# wemos_Atmega_32_sensor_tes_2.net
KiCad netlist of a schematic drawn in EAGLE
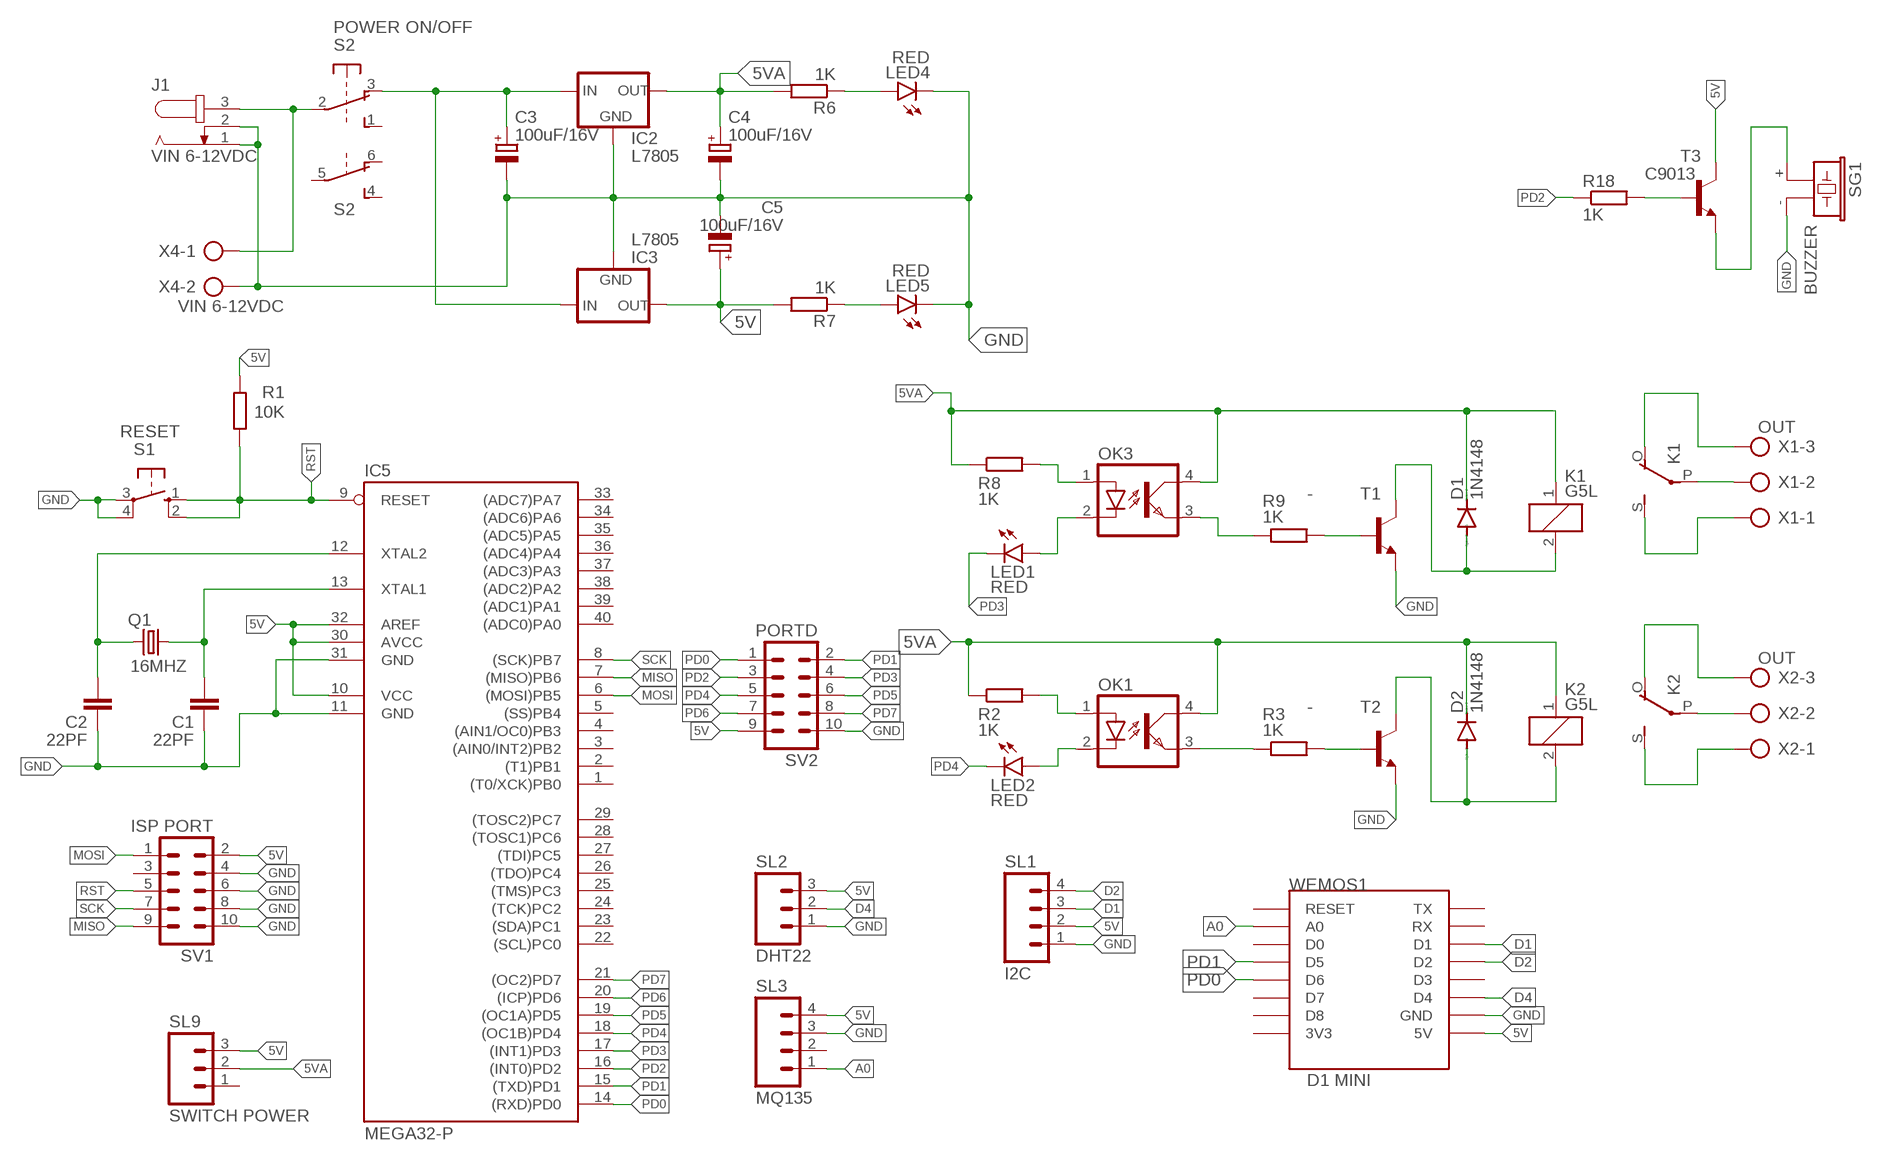
[diagram p0: schematic, sheet 1]

(export (version "E")
  (design (tool "Eeschema 10.0.6"))
  (components
    (comp (ref "C1")
      (value "22PF")
      (footprint "eagle-import:C2.5-2")
      (libsource (lib "eagle-import") (part "C2.5/2"))
    )
    (comp (ref "C2")
      (value "22PF")
      (footprint "eagle-import:C2.5-2")
      (libsource (lib "eagle-import") (part "C2.5/2"))
    )
    (comp (ref "C3")
      (value "100uF/16V")
      (footprint "eagle-import:E2,5-6E")
      (libsource (lib "eagle-import") (part "CPOL-EUE2,5-6E"))
    )
    (comp (ref "C4")
      (value "100uF/16V")
      (footprint "eagle-import:E2,5-6E")
      (libsource (lib "eagle-import") (part "CPOL-EUE2,5-6E"))
    )
    (comp (ref "C5")
      (value "100uF/16V")
      (footprint "eagle-import:E2,5-6E")
      (libsource (lib "eagle-import") (part "CPOL-EUE2,5-6E"))
    )
    (comp (ref "D1")
      (value "1N4148")
      (footprint "eagle-import:SOD123")
      (libsource (lib "eagle-import") (part "DIODE-SOD123"))
    )
    (comp (ref "D2")
      (value "1N4148")
      (footprint "eagle-import:SOD123")
      (libsource (lib "eagle-import") (part "DIODE-SOD123"))
    )
    (comp (ref "IC2")
      (value "L7805")
      (footprint "eagle-import:78XXL")
      (libsource (lib "eagle-import") (part "78XXL"))
    )
    (comp (ref "IC3")
      (value "L7805")
      (footprint "eagle-import:78XXL")
      (libsource (lib "eagle-import") (part "78XXL"))
    )
    (comp (ref "IC5")
      (value "MEGA32-P")
      (footprint "eagle-import:DIL40")
      (fields (field (name "MPN") "ATMEGA32-16PU"))
      (libsource (lib "eagle-import") (part "MEGA32-P"))
    )
    (comp (ref "J1")
      (value "VIN 6-12VDC")
      (footprint "eagle-import:SPC4078")
      (libsource (lib "eagle-import") (part "JACK-PLUG1"))
    )
    (comp (ref "K1")
      (value "G5L")
      (footprint "eagle-import:G5LE")
      (libsource (lib "eagle-import") (part "G5L"))
    )
    (comp (ref "K2")
      (value "G5L")
      (footprint "eagle-import:G5LE")
      (libsource (lib "eagle-import") (part "G5L"))
    )
    (comp (ref "LED1")
      (value "RED")
      (footprint "eagle-import:LED3MM")
      (libsource (lib "eagle-import") (part "LED3MM"))
    )
    (comp (ref "LED2")
      (value "RED")
      (footprint "eagle-import:LED3MM")
      (libsource (lib "eagle-import") (part "LED3MM"))
    )
    (comp (ref "LED4")
      (value "RED")
      (footprint "eagle-import:LED3MM")
      (libsource (lib "eagle-import") (part "LED3MM"))
    )
    (comp (ref "LED5")
      (value "RED")
      (footprint "eagle-import:LED3MM")
      (libsource (lib "eagle-import") (part "LED3MM"))
    )
    (comp (ref "OK1")
      (value "PC817")
      (footprint "eagle-import:DIL04")
      (fields (field (name "MPN") "PC817X4J000F"))
      (libsource (lib "eagle-import") (part "PC817"))
    )
    (comp (ref "OK3")
      (value "PC817")
      (footprint "eagle-import:DIL04")
      (fields (field (name "MPN") "PC817X4J000F"))
      (libsource (lib "eagle-import") (part "PC817"))
    )
    (comp (ref "Q1")
      (value "16MHZ")
      (footprint "eagle-import:HC49_S")
      (libsource (lib "eagle-import") (part "CRYSTALHC49S"))
    )
    (comp (ref "R1")
      (value "10K")
      (footprint "eagle-import:R1206")
      (libsource (lib "eagle-import") (part "R-EU_R1206"))
    )
    (comp (ref "R2")
      (value "1K")
      (footprint "eagle-import:R1206")
      (libsource (lib "eagle-import") (part "R-EU_R1206"))
    )
    (comp (ref "R3")
      (value "1K")
      (footprint "eagle-import:R1206")
      (libsource (lib "eagle-import") (part "R-EU_R1206"))
    )
    (comp (ref "R6")
      (value "1K")
      (footprint "eagle-import:R1206")
      (libsource (lib "eagle-import") (part "R-EU_R1206"))
    )
    (comp (ref "R7")
      (value "1K")
      (footprint "eagle-import:R1206")
      (libsource (lib "eagle-import") (part "R-EU_R1206"))
    )
    (comp (ref "R8")
      (value "1K")
      (footprint "eagle-import:R1206")
      (libsource (lib "eagle-import") (part "R-EU_R1206"))
    )
    (comp (ref "R9")
      (value "1K")
      (footprint "eagle-import:R1206")
      (libsource (lib "eagle-import") (part "R-EU_R1206"))
    )
    (comp (ref "R18")
      (value "1K")
      (footprint "eagle-import:R1206")
      (libsource (lib "eagle-import") (part "R-EU_R1206"))
    )
    (comp (ref "S1")
      (value "RESET")
      (footprint "eagle-import:B3F-10XX")
      (fields (field (name "MPN") "B3F-1000"))
      (libsource (lib "eagle-import") (part "10-XX"))
    )
    (comp (ref "S2")
      (value "POWER ON/OFF")
      (footprint "eagle-import:9077-2")
      (libsource (lib "eagle-import") (part "9077-2"))
    )
    (comp (ref "SG1")
      (value "BUZZER")
      (footprint "eagle-import:F_CM12P")
      (libsource (lib "eagle-import") (part "F/CM12P"))
    )
    (comp (ref "SL1")
      (value "I2C")
      (footprint "eagle-import:04P")
      (libsource (lib "eagle-import") (part "M04"))
    )
    (comp (ref "SL2")
      (value "DHT22")
      (footprint "eagle-import:03P")
      (libsource (lib "eagle-import") (part "M03"))
    )
    (comp (ref "SL3")
      (value "MQ135")
      (footprint "eagle-import:04P")
      (libsource (lib "eagle-import") (part "M04"))
    )
    (comp (ref "SL9")
      (value "SWITCH POWER")
      (footprint "eagle-import:03P")
      (libsource (lib "eagle-import") (part "M03"))
    )
    (comp (ref "SV1")
      (value "ISP PORT")
      (footprint "eagle-import:ML10")
      (libsource (lib "eagle-import") (part "ML10"))
    )
    (comp (ref "SV2")
      (value "PORTD")
      (footprint "eagle-import:ML10")
      (libsource (lib "eagle-import") (part "ML10"))
    )
    (comp (ref "T1")
      (value "-")
      (footprint "eagle-import:SOT23-BEC")
      (libsource (lib "eagle-import") (part "-NPN-SOT23-BECBC808"))
    )
    (comp (ref "T2")
      (value "-")
      (footprint "eagle-import:SOT23-BEC")
      (libsource (lib "eagle-import") (part "-NPN-SOT23-BECBC808"))
    )
    (comp (ref "T3")
      (value "C9013")
      (footprint "eagle-import:SOT23-BEC")
      (libsource (lib "eagle-import") (part "-NPN-SOT23-BECBC808"))
    )
    (comp (ref "WEMOS1")
      (value "D1 MINI")
      (footprint "eagle-import:WEMOS-D1-MINI")
      (libsource (lib "eagle-import") (part "WEMOS-D1-MINI"))
    )
    (comp (ref "X1")
      (value "OUT")
      (footprint "eagle-import:AK500_3")
      (libsource (lib "eagle-import") (part "AK500/3"))
    )
    (comp (ref "X2")
      (value "OUT")
      (footprint "eagle-import:AK500_3")
      (libsource (lib "eagle-import") (part "AK500/3"))
    )
    (comp (ref "X4")
      (value "VIN 6-12VDC")
      (footprint "eagle-import:AK500_2")
      (libsource (lib "eagle-import") (part "AK500/2"))
    )
  )
  (nets
    (net (code "1") (name "5V") (class "Default")
      (node (ref "C5") (pin "+") (pinfunction "+_+") (pintype "passive"))
      (node (ref "IC3") (pin "OUT") (pinfunction "OUT_OUT") (pintype "passive"))
      (node (ref "IC5") (pin "10") (pinfunction "VCC_10") (pintype "power_in"))
      (node (ref "IC5") (pin "30") (pinfunction "AVCC_30") (pintype "power_in"))
      (node (ref "IC5") (pin "32") (pinfunction "AREF_32") (pintype "passive"))
      (node (ref "R1") (pin "2") (pinfunction "2_2") (pintype "passive"))
      (node (ref "R7") (pin "2") (pinfunction "2_2") (pintype "passive"))
      (node (ref "SL1") (pin "2") (pinfunction "2_2") (pintype "passive"))
      (node (ref "SL2") (pin "3") (pinfunction "3_3") (pintype "passive"))
      (node (ref "SL3") (pin "4") (pinfunction "4_4") (pintype "passive"))
      (node (ref "SL9") (pin "3") (pinfunction "3_3") (pintype "passive"))
      (node (ref "SV1") (pin "2") (pinfunction "2_2") (pintype "passive"))
      (node (ref "SV2") (pin "9") (pinfunction "9_9") (pintype "passive"))
      (node (ref "T3") (pin "C") (pinfunction "C_C") (pintype "passive"))
      (node (ref "WEMOS1") (pin "5V") (pinfunction "5V_5V") (pintype "bidirectional"))
    )
    (net (code "2") (name "5VA") (class "Default")
      (node (ref "C4") (pin "+") (pinfunction "+_+") (pintype "passive"))
      (node (ref "D1") (pin "C") (pinfunction "C_C") (pintype "passive"))
      (node (ref "D2") (pin "C") (pinfunction "C_C") (pintype "passive"))
      (node (ref "IC2") (pin "OUT") (pinfunction "OUT_OUT") (pintype "passive"))
      (node (ref "K1") (pin "1") (pinfunction "1_1") (pintype "passive"))
      (node (ref "K2") (pin "1") (pinfunction "1_1") (pintype "passive"))
      (node (ref "OK1") (pin "4") (pinfunction "COL_4") (pintype "passive"))
      (node (ref "OK3") (pin "4") (pinfunction "COL_4") (pintype "passive"))
      (node (ref "R2") (pin "1") (pinfunction "1_1") (pintype "passive"))
      (node (ref "R6") (pin "2") (pinfunction "2_2") (pintype "passive"))
      (node (ref "R8") (pin "1") (pinfunction "1_1") (pintype "passive"))
      (node (ref "SL9") (pin "2") (pinfunction "2_2") (pintype "passive"))
    )
    (net (code "3") (name "A0") (class "Default")
      (node (ref "SL3") (pin "1") (pinfunction "1_1") (pintype "passive"))
      (node (ref "WEMOS1") (pin "A0") (pinfunction "A0_A0") (pintype "bidirectional"))
    )
    (net (code "4") (name "D1") (class "Default")
      (node (ref "SL1") (pin "3") (pinfunction "3_3") (pintype "passive"))
      (node (ref "WEMOS1") (pin "D1") (pinfunction "D1_D1") (pintype "bidirectional"))
    )
    (net (code "5") (name "D2") (class "Default")
      (node (ref "SL1") (pin "4") (pinfunction "4_4") (pintype "passive"))
      (node (ref "WEMOS1") (pin "D2") (pinfunction "D2_D2") (pintype "bidirectional"))
    )
    (net (code "6") (name "D4") (class "Default")
      (node (ref "SL2") (pin "2") (pinfunction "2_2") (pintype "passive"))
      (node (ref "WEMOS1") (pin "D4") (pinfunction "D4_D4") (pintype "bidirectional"))
    )
    (net (code "7") (name "GND") (class "Default")
      (node (ref "C1") (pin "1") (pinfunction "1_1") (pintype "passive"))
      (node (ref "C2") (pin "1") (pinfunction "1_1") (pintype "passive"))
      (node (ref "C3") (pin "-") (pinfunction "-_-") (pintype "passive"))
      (node (ref "C4") (pin "-") (pinfunction "-_-") (pintype "passive"))
      (node (ref "C5") (pin "-") (pinfunction "-_-") (pintype "passive"))
      (node (ref "IC2") (pin "GND") (pinfunction "GND_GND") (pintype "input"))
      (node (ref "IC3") (pin "GND") (pinfunction "GND_GND") (pintype "input"))
      (node (ref "IC5") (pin "11") (pinfunction "GND_11") (pintype "power_in"))
      (node (ref "IC5") (pin "31") (pinfunction "GND_31") (pintype "power_in"))
      (node (ref "J1") (pin "1") (pinfunction "1_1") (pintype "passive"))
      (node (ref "J1") (pin "2") (pinfunction "2_2") (pintype "passive"))
      (node (ref "LED4") (pin "K") (pinfunction "C_K") (pintype "passive"))
      (node (ref "LED5") (pin "K") (pinfunction "C_K") (pintype "passive"))
      (node (ref "S1") (pin "3") (pinfunction "P_3") (pintype "passive"))
      (node (ref "S1") (pin "4") (pinfunction "P1_4") (pintype "passive"))
      (node (ref "SG1") (pin "-") (pinfunction "2_-") (pintype "passive"))
      (node (ref "SL1") (pin "1") (pinfunction "1_1") (pintype "passive"))
      (node (ref "SL2") (pin "1") (pinfunction "1_1") (pintype "passive"))
      (node (ref "SL3") (pin "3") (pinfunction "3_3") (pintype "passive"))
      (node (ref "SV1") (pin "10") (pinfunction "10_10") (pintype "passive"))
      (node (ref "SV1") (pin "4") (pinfunction "4_4") (pintype "passive"))
      (node (ref "SV1") (pin "6") (pinfunction "6_6") (pintype "passive"))
      (node (ref "SV1") (pin "8") (pinfunction "8_8") (pintype "passive"))
      (node (ref "SV2") (pin "10") (pinfunction "10_10") (pintype "passive"))
      (node (ref "T1") (pin "E") (pinfunction "E_E") (pintype "passive"))
      (node (ref "T2") (pin "E") (pinfunction "E_E") (pintype "passive"))
      (node (ref "WEMOS1") (pin "GND") (pinfunction "GND_GND") (pintype "bidirectional"))
      (node (ref "X4") (pin "2") (pinfunction "KL_2") (pintype "passive"))
    )
    (net (code "8") (name "MISO") (class "Default")
      (node (ref "IC5") (pin "7") (pinfunction "(MISO)PB6_7") (pintype "bidirectional"))
      (node (ref "SV1") (pin "9") (pinfunction "9_9") (pintype "passive"))
    )
    (net (code "9") (name "MOSI") (class "Default")
      (node (ref "IC5") (pin "6") (pinfunction "(MOSI)PB5_6") (pintype "bidirectional"))
      (node (ref "SV1") (pin "1") (pinfunction "1_1") (pintype "passive"))
    )
    (net (code "10") (name "Net-(D1-PadA)") (class "Default")
      (node (ref "D1") (pin "A") (pinfunction "A_A") (pintype "passive"))
      (node (ref "K1") (pin "2") (pinfunction "2_2") (pintype "passive"))
      (node (ref "T1") (pin "C") (pinfunction "C_C") (pintype "passive"))
    )
    (net (code "11") (name "Net-(D2-PadA)") (class "Default")
      (node (ref "D2") (pin "A") (pinfunction "A_A") (pintype "passive"))
      (node (ref "K2") (pin "2") (pinfunction "2_2") (pintype "passive"))
      (node (ref "T2") (pin "C") (pinfunction "C_C") (pintype "passive"))
    )
    (net (code "12") (name "Net-(IC5-XTAL1)") (class "Default")
      (node (ref "C1") (pin "2") (pinfunction "2_2") (pintype "passive"))
      (node (ref "IC5") (pin "13") (pinfunction "XTAL1_13") (pintype "bidirectional"))
      (node (ref "Q1") (pin "1") (pinfunction "1_1") (pintype "passive"))
    )
    (net (code "13") (name "Net-(IC5-XTAL2)") (class "Default")
      (node (ref "C2") (pin "2") (pinfunction "2_2") (pintype "passive"))
      (node (ref "IC5") (pin "12") (pinfunction "XTAL2_12") (pintype "bidirectional"))
      (node (ref "Q1") (pin "2") (pinfunction "2_2") (pintype "passive"))
    )
    (net (code "14") (name "Net-(LED4-PadA)") (class "Default")
      (node (ref "LED4") (pin "A") (pinfunction "A_A") (pintype "passive"))
      (node (ref "R6") (pin "1") (pinfunction "1_1") (pintype "passive"))
    )
    (net (code "15") (name "Net-(LED5-PadA)") (class "Default")
      (node (ref "LED5") (pin "A") (pinfunction "A_A") (pintype "passive"))
      (node (ref "R7") (pin "1") (pinfunction "1_1") (pintype "passive"))
    )
    (net (code "16") (name "Net-(OK1-A)") (class "Default")
      (node (ref "OK1") (pin "1") (pinfunction "A_1") (pintype "passive"))
      (node (ref "R2") (pin "2") (pinfunction "2_2") (pintype "passive"))
    )
    (net (code "17") (name "Net-(OK1-C)") (class "Default")
      (node (ref "LED2") (pin "A") (pinfunction "A_A") (pintype "passive"))
      (node (ref "OK1") (pin "2") (pinfunction "C_2") (pintype "passive"))
    )
    (net (code "18") (name "Net-(OK1-EMIT)") (class "Default")
      (node (ref "OK1") (pin "3") (pinfunction "EMIT_3") (pintype "passive"))
      (node (ref "R3") (pin "1") (pinfunction "1_1") (pintype "passive"))
    )
    (net (code "19") (name "Net-(OK3-A)") (class "Default")
      (node (ref "OK3") (pin "1") (pinfunction "A_1") (pintype "passive"))
      (node (ref "R8") (pin "2") (pinfunction "2_2") (pintype "passive"))
    )
    (net (code "20") (name "Net-(OK3-C)") (class "Default")
      (node (ref "LED1") (pin "A") (pinfunction "A_A") (pintype "passive"))
      (node (ref "OK3") (pin "2") (pinfunction "C_2") (pintype "passive"))
    )
    (net (code "21") (name "Net-(OK3-EMIT)") (class "Default")
      (node (ref "OK3") (pin "3") (pinfunction "EMIT_3") (pintype "passive"))
      (node (ref "R9") (pin "1") (pinfunction "1_1") (pintype "passive"))
    )
    (net (code "22") (name "Net-(R3-Pad2)") (class "Default")
      (node (ref "R3") (pin "2") (pinfunction "2_2") (pintype "passive"))
      (node (ref "T2") (pin "B") (pinfunction "B_B") (pintype "passive"))
    )
    (net (code "23") (name "Net-(R9-Pad2)") (class "Default")
      (node (ref "R9") (pin "2") (pinfunction "2_2") (pintype "passive"))
      (node (ref "T1") (pin "B") (pinfunction "B_B") (pintype "passive"))
    )
    (net (code "24") (name "Net-(R18-Pad2)") (class "Default")
      (node (ref "R18") (pin "2") (pinfunction "2_2") (pintype "passive"))
      (node (ref "T3") (pin "B") (pinfunction "B_B") (pintype "passive"))
    )
    (net (code "25") (name "Net-(S2A-O)") (class "Default")
      (node (ref "C3") (pin "+") (pinfunction "+_+") (pintype "passive"))
      (node (ref "IC2") (pin "IN") (pinfunction "IN_IN") (pintype "input"))
      (node (ref "IC3") (pin "IN") (pinfunction "IN_IN") (pintype "input"))
      (node (ref "S2") (pin "3") (pinfunction "O_3") (pintype "passive"))
    )
    (net (code "26") (name "Net-(S2A-P)") (class "Default")
      (node (ref "J1") (pin "3") (pinfunction "3_3") (pintype "passive"))
      (node (ref "S2") (pin "2") (pinfunction "P_2") (pintype "passive"))
      (node (ref "X4") (pin "1") (pinfunction "KL_1") (pintype "passive"))
    )
    (net (code "27") (name "Net-(SG1-1)") (class "Default")
      (node (ref "SG1") (pin "+") (pinfunction "1_+") (pintype "passive"))
      (node (ref "T3") (pin "E") (pinfunction "E_E") (pintype "passive"))
    )
    (net (code "28") (name "Net-(X1A-KL)") (class "Default")
      (node (ref "K1") (pin "S") (pinfunction "S_S") (pintype "passive"))
      (node (ref "X1") (pin "1") (pinfunction "KL_1") (pintype "passive"))
    )
    (net (code "29") (name "Net-(X1B-KL)") (class "Default")
      (node (ref "K1") (pin "P") (pinfunction "P_P") (pintype "passive"))
      (node (ref "X1") (pin "2") (pinfunction "KL_2") (pintype "passive"))
    )
    (net (code "30") (name "Net-(X1C-KL)") (class "Default")
      (node (ref "K1") (pin "O") (pinfunction "O_O") (pintype "passive"))
      (node (ref "X1") (pin "3") (pinfunction "KL_3") (pintype "passive"))
    )
    (net (code "31") (name "Net-(X2A-KL)") (class "Default")
      (node (ref "K2") (pin "S") (pinfunction "S_S") (pintype "passive"))
      (node (ref "X2") (pin "1") (pinfunction "KL_1") (pintype "passive"))
    )
    (net (code "32") (name "Net-(X2B-KL)") (class "Default")
      (node (ref "K2") (pin "P") (pinfunction "P_P") (pintype "passive"))
      (node (ref "X2") (pin "2") (pinfunction "KL_2") (pintype "passive"))
    )
    (net (code "33") (name "Net-(X2C-KL)") (class "Default")
      (node (ref "K2") (pin "O") (pinfunction "O_O") (pintype "passive"))
      (node (ref "X2") (pin "3") (pinfunction "KL_3") (pintype "passive"))
    )
    (net (code "34") (name "PD0") (class "Default")
      (node (ref "IC5") (pin "14") (pinfunction "(RXD)PD0_14") (pintype "bidirectional"))
      (node (ref "SV2") (pin "1") (pinfunction "1_1") (pintype "passive"))
      (node (ref "WEMOS1") (pin "D6") (pinfunction "D6_D6") (pintype "bidirectional"))
    )
    (net (code "35") (name "PD1") (class "Default")
      (node (ref "IC5") (pin "15") (pinfunction "(TXD)PD1_15") (pintype "bidirectional"))
      (node (ref "SV2") (pin "2") (pinfunction "2_2") (pintype "passive"))
      (node (ref "WEMOS1") (pin "D5") (pinfunction "D5_D5") (pintype "bidirectional"))
    )
    (net (code "36") (name "PD2") (class "Default")
      (node (ref "IC5") (pin "16") (pinfunction "(INT0)PD2_16") (pintype "bidirectional"))
      (node (ref "R18") (pin "1") (pinfunction "1_1") (pintype "passive"))
      (node (ref "SV2") (pin "3") (pinfunction "3_3") (pintype "passive"))
    )
    (net (code "37") (name "PD3") (class "Default")
      (node (ref "IC5") (pin "17") (pinfunction "(INT1)PD3_17") (pintype "bidirectional"))
      (node (ref "LED1") (pin "K") (pinfunction "C_K") (pintype "passive"))
      (node (ref "SV2") (pin "4") (pinfunction "4_4") (pintype "passive"))
    )
    (net (code "38") (name "PD4") (class "Default")
      (node (ref "IC5") (pin "18") (pinfunction "(OC1B)PD4_18") (pintype "bidirectional"))
      (node (ref "LED2") (pin "K") (pinfunction "C_K") (pintype "passive"))
      (node (ref "SV2") (pin "5") (pinfunction "5_5") (pintype "passive"))
    )
    (net (code "39") (name "PD5") (class "Default")
      (node (ref "IC5") (pin "19") (pinfunction "(OC1A)PD5_19") (pintype "bidirectional"))
      (node (ref "SV2") (pin "6") (pinfunction "6_6") (pintype "passive"))
    )
    (net (code "40") (name "PD6") (class "Default")
      (node (ref "IC5") (pin "20") (pinfunction "(ICP)PD6_20") (pintype "bidirectional"))
      (node (ref "SV2") (pin "7") (pinfunction "7_7") (pintype "passive"))
    )
    (net (code "41") (name "PD7") (class "Default")
      (node (ref "IC5") (pin "21") (pinfunction "(OC2)PD7_21") (pintype "bidirectional"))
      (node (ref "SV2") (pin "8") (pinfunction "8_8") (pintype "passive"))
    )
    (net (code "42") (name "RST") (class "Default")
      (node (ref "IC5") (pin "9") (pinfunction "RESET_9") (pintype "input"))
      (node (ref "R1") (pin "1") (pinfunction "1_1") (pintype "passive"))
      (node (ref "S1") (pin "1") (pinfunction "S_1") (pintype "passive"))
      (node (ref "S1") (pin "2") (pinfunction "S1_2") (pintype "passive"))
      (node (ref "SV1") (pin "5") (pinfunction "5_5") (pintype "passive"))
    )
    (net (code "43") (name "SCK") (class "Default")
      (node (ref "IC5") (pin "8") (pinfunction "(SCK)PB7_8") (pintype "bidirectional"))
      (node (ref "SV1") (pin "7") (pinfunction "7_7") (pintype "passive"))
    )
    (net (code "44") (name "unconnected-(IC5-(ADC0)PA0-Pad40)") (class "Default")
      (node (ref "IC5") (pin "40") (pinfunction "(ADC0)PA0_40") (pintype "bidirectional"))
    )
    (net (code "45") (name "unconnected-(IC5-(ADC1)PA1-Pad39)") (class "Default")
      (node (ref "IC5") (pin "39") (pinfunction "(ADC1)PA1_39") (pintype "bidirectional"))
    )
    (net (code "46") (name "unconnected-(IC5-(ADC2)PA2-Pad38)") (class "Default")
      (node (ref "IC5") (pin "38") (pinfunction "(ADC2)PA2_38") (pintype "bidirectional"))
    )
    (net (code "47") (name "unconnected-(IC5-(ADC3)PA3-Pad37)") (class "Default")
      (node (ref "IC5") (pin "37") (pinfunction "(ADC3)PA3_37") (pintype "bidirectional"))
    )
    (net (code "48") (name "unconnected-(IC5-(ADC4)PA4-Pad36)") (class "Default")
      (node (ref "IC5") (pin "36") (pinfunction "(ADC4)PA4_36") (pintype "bidirectional"))
    )
    (net (code "49") (name "unconnected-(IC5-(ADC5)PA5-Pad35)") (class "Default")
      (node (ref "IC5") (pin "35") (pinfunction "(ADC5)PA5_35") (pintype "bidirectional"))
    )
    (net (code "50") (name "unconnected-(IC5-(ADC6)PA6-Pad34)") (class "Default")
      (node (ref "IC5") (pin "34") (pinfunction "(ADC6)PA6_34") (pintype "bidirectional"))
    )
    (net (code "51") (name "unconnected-(IC5-(ADC7)PA7-Pad33)") (class "Default")
      (node (ref "IC5") (pin "33") (pinfunction "(ADC7)PA7_33") (pintype "bidirectional"))
    )
    (net (code "52") (name "unconnected-(IC5-(AIN0{slash}INT2)PB2-Pad3)") (class "Default")
      (node (ref "IC5") (pin "3") (pinfunction "(AIN0/INT2)PB2_3") (pintype "bidirectional"))
    )
    (net (code "53") (name "unconnected-(IC5-(AIN1{slash}OC0)PB3-Pad4)") (class "Default")
      (node (ref "IC5") (pin "4") (pinfunction "(AIN1/OC0)PB3_4") (pintype "bidirectional"))
    )
    (net (code "54") (name "unconnected-(IC5-(SCL)PC0-Pad22)") (class "Default")
      (node (ref "IC5") (pin "22") (pinfunction "(SCL)PC0_22") (pintype "bidirectional"))
    )
    (net (code "55") (name "unconnected-(IC5-(SDA)PC1-Pad23)") (class "Default")
      (node (ref "IC5") (pin "23") (pinfunction "(SDA)PC1_23") (pintype "bidirectional"))
    )
    (net (code "56") (name "unconnected-(IC5-(SS)PB4-Pad5)") (class "Default")
      (node (ref "IC5") (pin "5") (pinfunction "(SS)PB4_5") (pintype "bidirectional"))
    )
    (net (code "57") (name "unconnected-(IC5-(T0{slash}XCK)PB0-Pad1)") (class "Default")
      (node (ref "IC5") (pin "1") (pinfunction "(T0/XCK)PB0_1") (pintype "bidirectional"))
    )
    (net (code "58") (name "unconnected-(IC5-(T1)PB1-Pad2)") (class "Default")
      (node (ref "IC5") (pin "2") (pinfunction "(T1)PB1_2") (pintype "bidirectional"))
    )
    (net (code "59") (name "unconnected-(IC5-(TCK)PC2-Pad24)") (class "Default")
      (node (ref "IC5") (pin "24") (pinfunction "(TCK)PC2_24") (pintype "bidirectional"))
    )
    (net (code "60") (name "unconnected-(IC5-(TDI)PC5-Pad27)") (class "Default")
      (node (ref "IC5") (pin "27") (pinfunction "(TDI)PC5_27") (pintype "bidirectional"))
    )
    (net (code "61") (name "unconnected-(IC5-(TDO)PC4-Pad26)") (class "Default")
      (node (ref "IC5") (pin "26") (pinfunction "(TDO)PC4_26") (pintype "bidirectional"))
    )
    (net (code "62") (name "unconnected-(IC5-(TMS)PC3-Pad25)") (class "Default")
      (node (ref "IC5") (pin "25") (pinfunction "(TMS)PC3_25") (pintype "bidirectional"))
    )
    (net (code "63") (name "unconnected-(IC5-(TOSC1)PC6-Pad28)") (class "Default")
      (node (ref "IC5") (pin "28") (pinfunction "(TOSC1)PC6_28") (pintype "bidirectional"))
    )
    (net (code "64") (name "unconnected-(IC5-(TOSC2)PC7-Pad29)") (class "Default")
      (node (ref "IC5") (pin "29") (pinfunction "(TOSC2)PC7_29") (pintype "bidirectional"))
    )
    (net (code "65") (name "unconnected-(S2A-S-Pad1)") (class "Default")
      (node (ref "S2") (pin "1") (pinfunction "S_1") (pintype "passive"))
    )
    (net (code "66") (name "unconnected-(S2B-O-Pad6)") (class "Default")
      (node (ref "S2") (pin "6") (pinfunction "O_6") (pintype "passive"))
    )
    (net (code "67") (name "unconnected-(S2B-P-Pad5)") (class "Default")
      (node (ref "S2") (pin "5") (pinfunction "P_5") (pintype "passive"))
    )
    (net (code "68") (name "unconnected-(S2B-S-Pad4)") (class "Default")
      (node (ref "S2") (pin "4") (pinfunction "S_4") (pintype "passive"))
    )
    (net (code "69") (name "unconnected-(SL3-Pad2)") (class "Default")
      (node (ref "SL3") (pin "2") (pinfunction "2_2") (pintype "passive"))
    )
    (net (code "70") (name "unconnected-(SL9-Pad1)") (class "Default")
      (node (ref "SL9") (pin "1") (pinfunction "1_1") (pintype "passive"))
    )
    (net (code "71") (name "unconnected-(SV1-Pad3)") (class "Default")
      (node (ref "SV1") (pin "3") (pinfunction "3_3") (pintype "passive"))
    )
    (net (code "72") (name "unconnected-(WEMOS1-Pad3V3)") (class "Default")
      (node (ref "WEMOS1") (pin "3V3") (pinfunction "3V3_3V3") (pintype "bidirectional"))
    )
    (net (code "73") (name "unconnected-(WEMOS1-PadD0)") (class "Default")
      (node (ref "WEMOS1") (pin "D0") (pinfunction "D0_D0") (pintype "bidirectional"))
    )
    (net (code "74") (name "unconnected-(WEMOS1-PadD3)") (class "Default")
      (node (ref "WEMOS1") (pin "D3") (pinfunction "D3_D3") (pintype "bidirectional"))
    )
    (net (code "75") (name "unconnected-(WEMOS1-PadD7)") (class "Default")
      (node (ref "WEMOS1") (pin "D7") (pinfunction "D7_D7") (pintype "bidirectional"))
    )
    (net (code "76") (name "unconnected-(WEMOS1-PadD8)") (class "Default")
      (node (ref "WEMOS1") (pin "D8") (pinfunction "D8_D8") (pintype "bidirectional"))
    )
    (net (code "77") (name "unconnected-(WEMOS1-PadRESET)") (class "Default")
      (node (ref "WEMOS1") (pin "RESET") (pinfunction "RESET_RESET") (pintype "bidirectional"))
    )
    (net (code "78") (name "unconnected-(WEMOS1-PadRX)") (class "Default")
      (node (ref "WEMOS1") (pin "RX") (pinfunction "RX_RX") (pintype "bidirectional"))
    )
    (net (code "79") (name "unconnected-(WEMOS1-PadTX)") (class "Default")
      (node (ref "WEMOS1") (pin "TX") (pinfunction "TX_TX") (pintype "bidirectional"))
    )
  )
)
